# C128_Keyb_Test_SMD.net
KiCad netlist of a schematic drawn in EAGLE
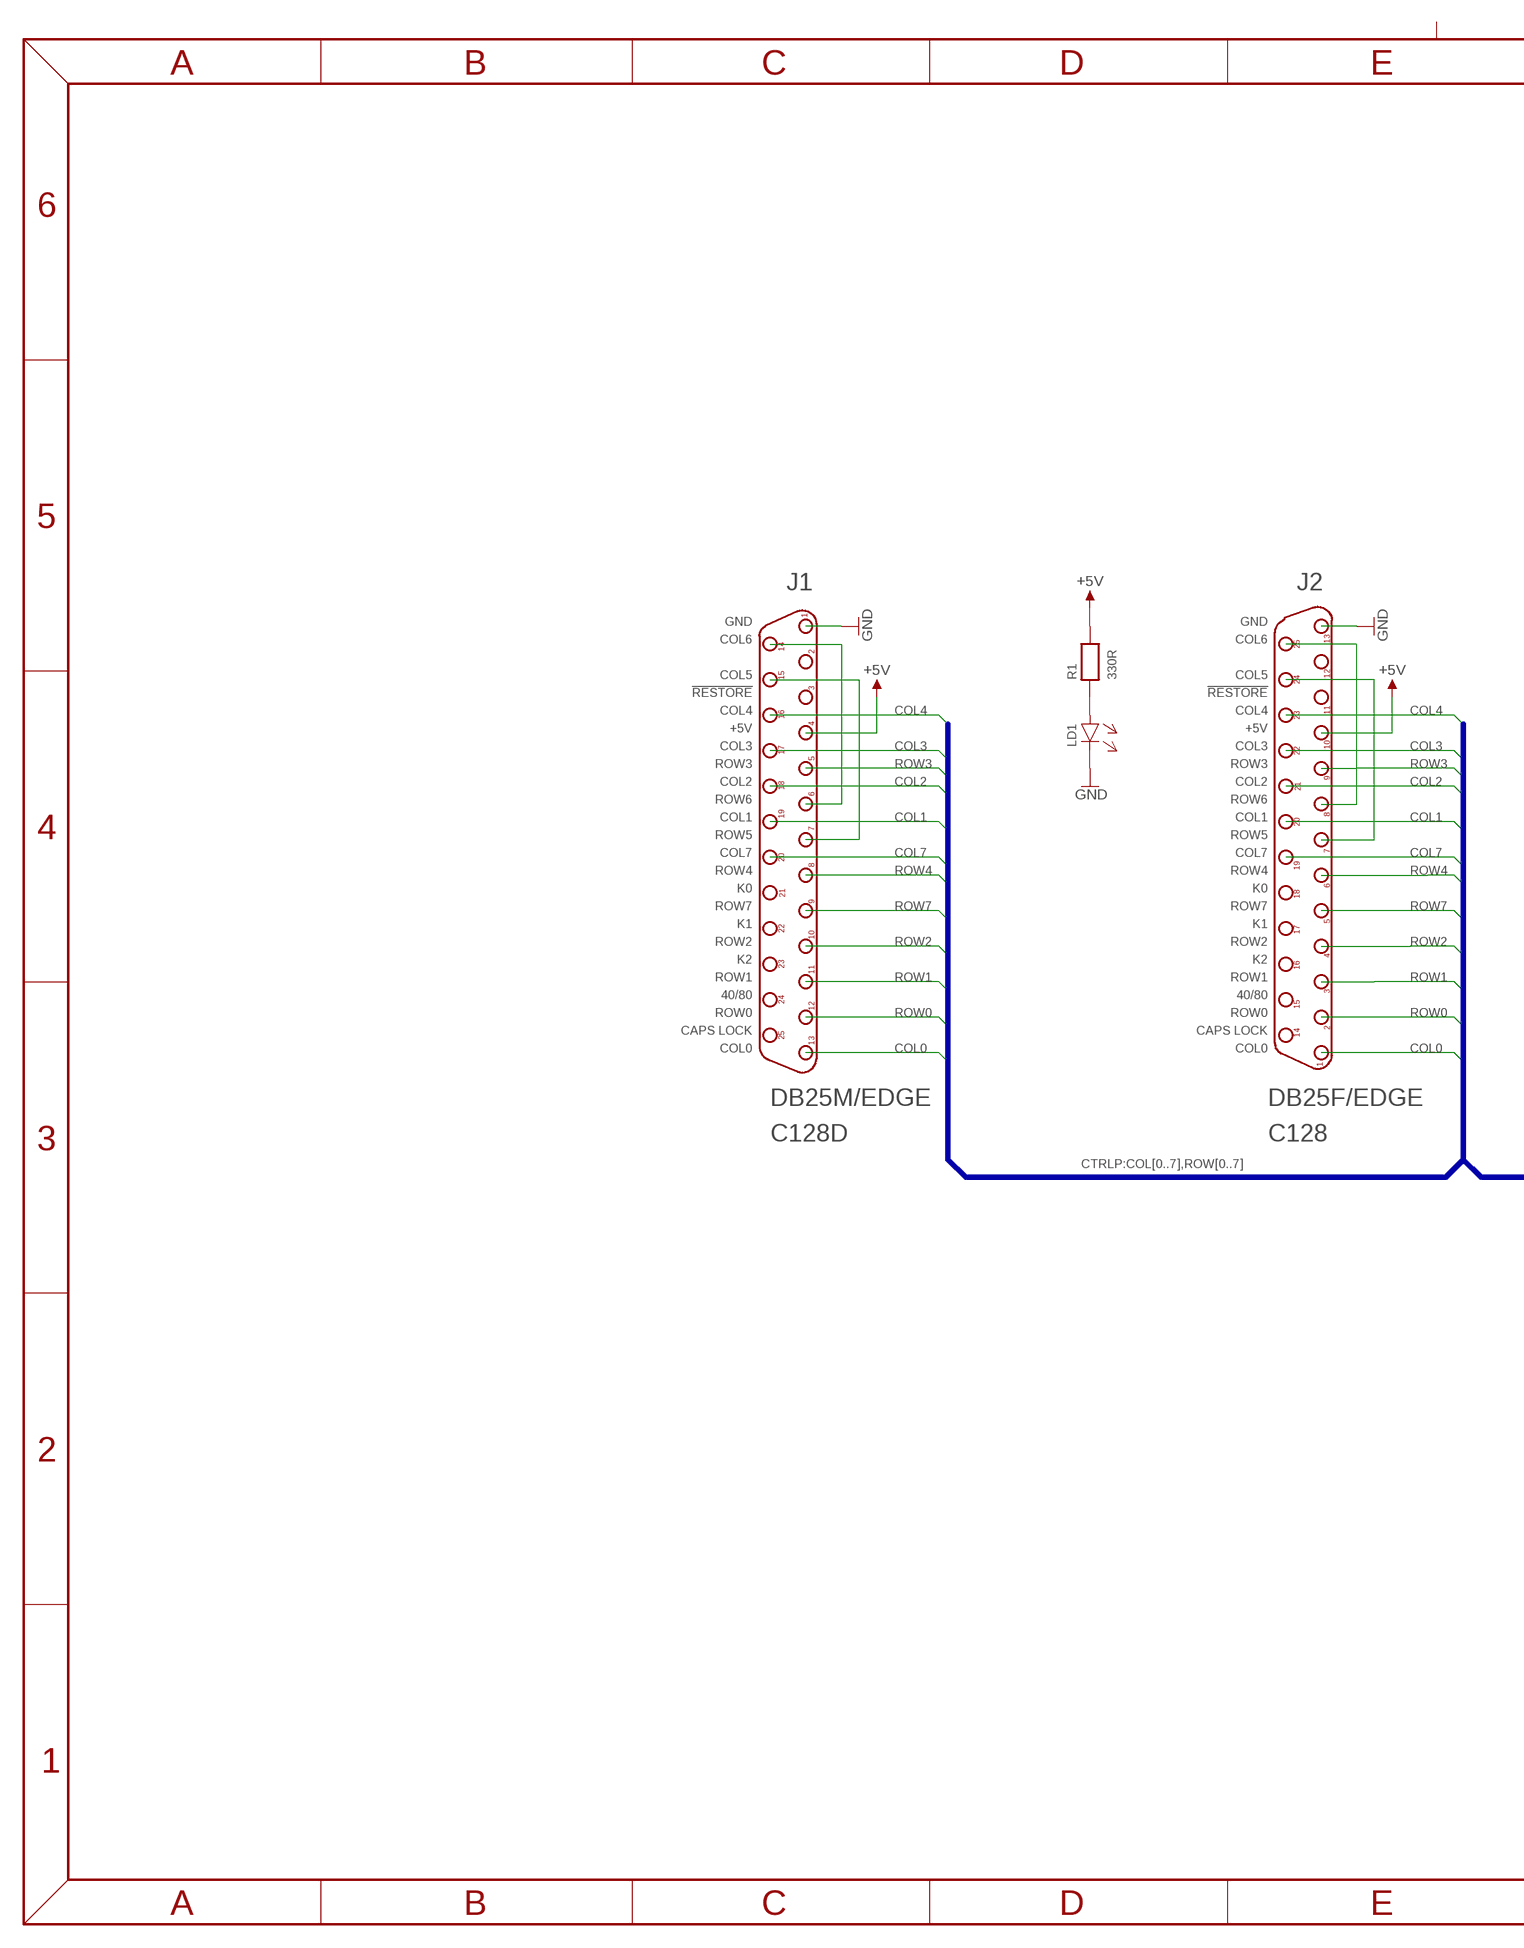
[diagram p0: schematic, sheet 1, part 1 of 2]
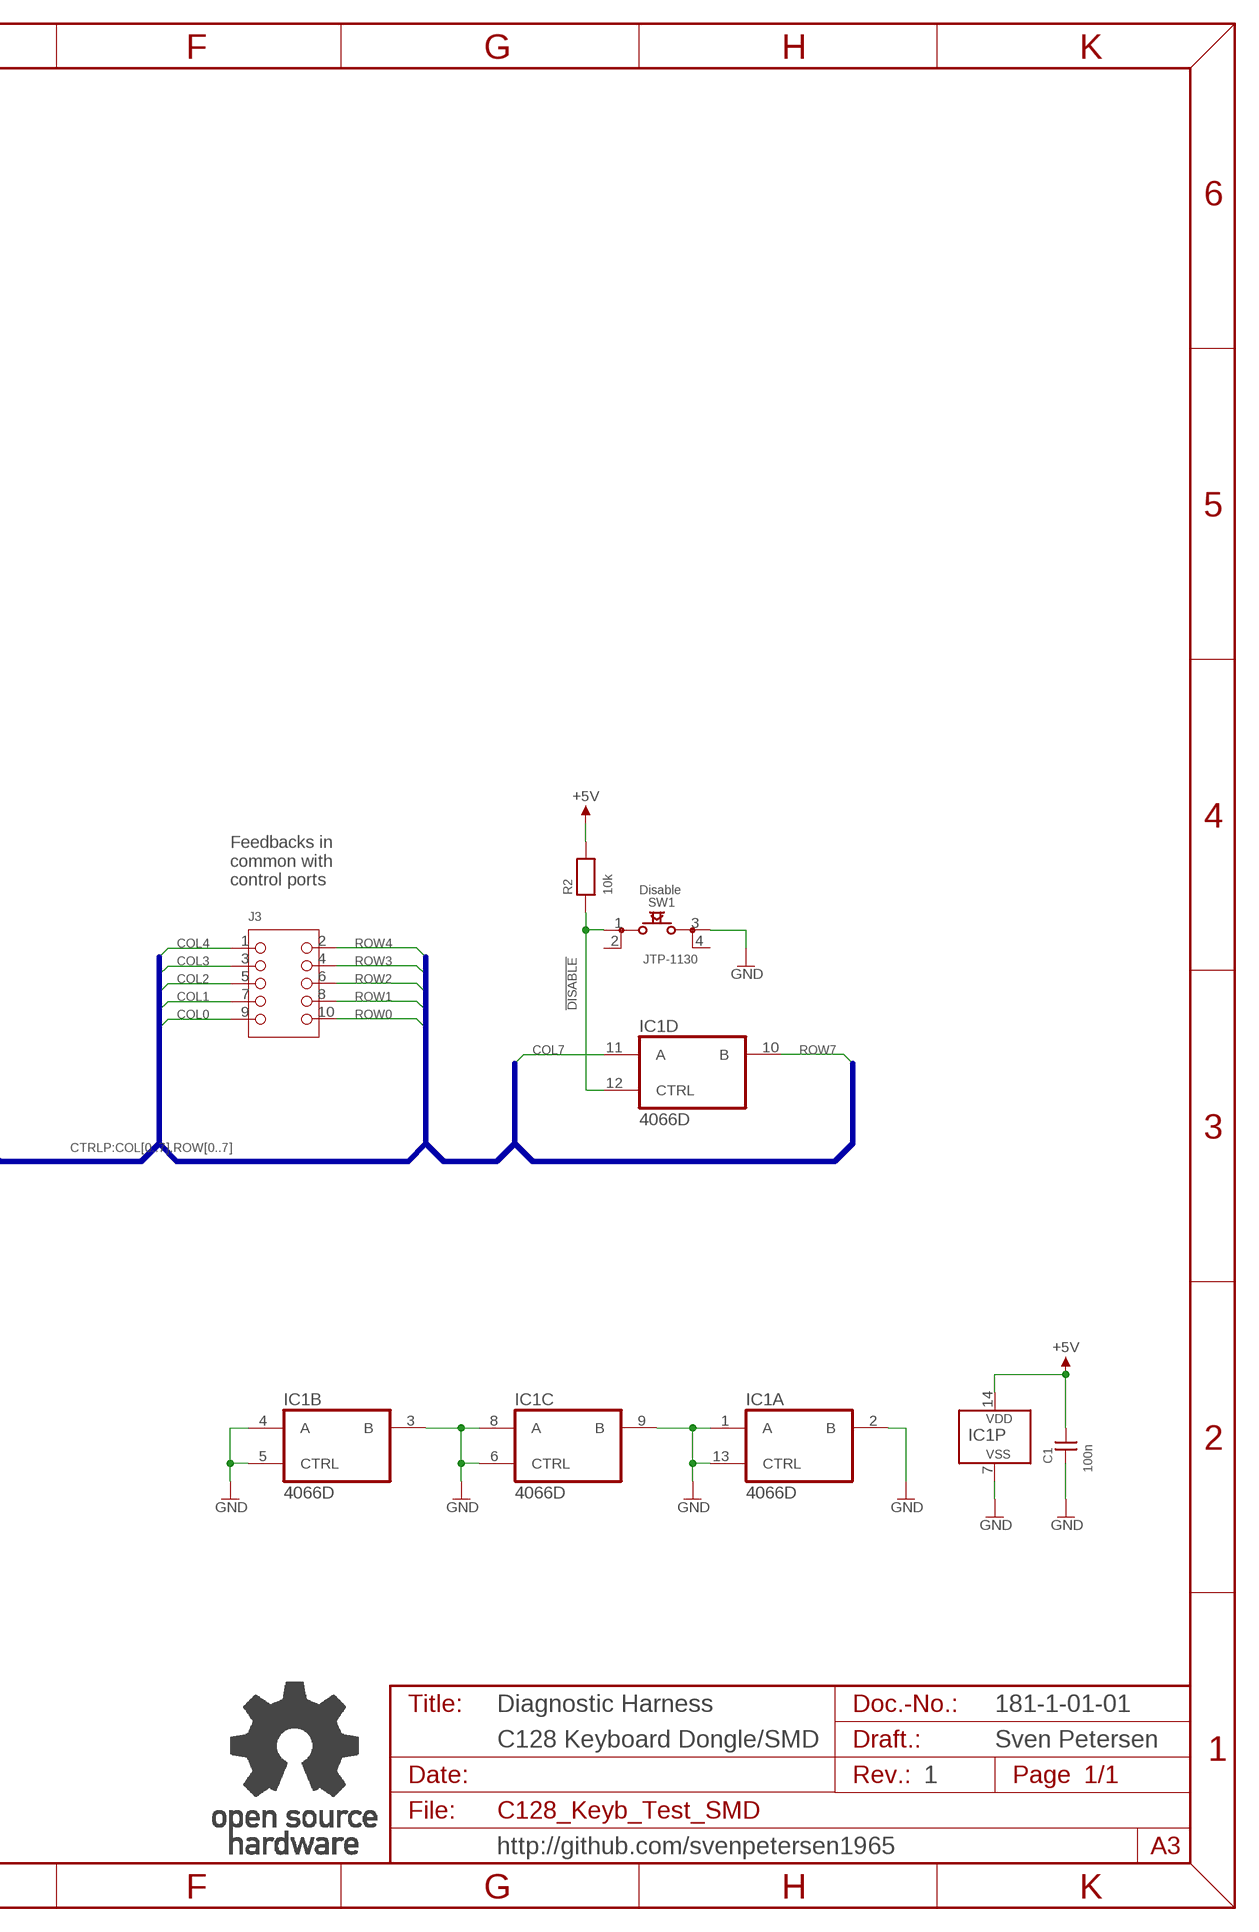
[diagram p1: schematic, sheet 1, part 2 of 2]

(export (version "E")
  (design (tool "Eeschema 10.0.6"))
  (components
    (comp (ref "C1")
      (value "100n")
      (footprint "eagle-import:0805")
      (libsource (lib "eagle-import") (part "CAP010805"))
    )
    (comp (ref "IC1")
      (value "4066D")
      (footprint "eagle-import:SO14")
      (libsource (lib "eagle-import") (part "4066D"))
    )
    (comp (ref "J1")
      (value "DB25M/EDGE")
      (footprint "eagle-import:DB25M-EDGE")
      (libsource (lib "eagle-import") (part "DB25M/EDGE"))
    )
    (comp (ref "J2")
      (value "DB25F/EDGE")
      (footprint "eagle-import:DB25F-EDGE")
      (libsource (lib "eagle-import") (part "DB25F/EDGE"))
    )
    (comp (ref "J3")
      (value "2X05WV")
      (footprint "eagle-import:2X05WV")
      (libsource (lib "eagle-import") (part "2X05WV"))
    )
    (comp (ref "LD1")
      (value "3MM")
      (footprint "eagle-import:3MM")
      (libsource (lib "eagle-import") (part "3MM"))
    )
    (comp (ref "R1")
      (value "330R")
      (footprint "eagle-import:0805")
      (libsource (lib "eagle-import") (part "RES040805"))
    )
    (comp (ref "R2")
      (value "10k")
      (footprint "eagle-import:0805")
      (libsource (lib "eagle-import") (part "RES040805"))
    )
    (comp (ref "SW1")
      (value "JTP-1130")
      (footprint "eagle-import:JTP-1130")
      (libsource (lib "eagle-import") (part "JTP-1130"))
    )
    (comp (ref "U$20")
      (value "OPEN_SOURCE_HW")
      (footprint "eagle-import:OPENHW")
      (libsource (lib "eagle-import") (part "OPEN_SOURCE_HW"))
    )
  )
  (nets
    (net (code "1") (name "+5V") (class "Default")
      (node (ref "C1") (pin "2") (pinfunction "2_2") (pintype "passive"))
      (node (ref "IC1") (pin "14") (pinfunction "VDD_14") (pintype "power_in"))
      (node (ref "J1") (pin "4") (pinfunction "4_4") (pintype "passive"))
      (node (ref "J2") (pin "10") (pinfunction "10_10") (pintype "passive"))
      (node (ref "R1") (pin "2") (pinfunction "2_2") (pintype "passive"))
      (node (ref "R2") (pin "2") (pinfunction "2_2") (pintype "passive"))
    )
    (net (code "2") (name "/COL0") (class "Default")
      (node (ref "J1") (pin "13") (pinfunction "13_13") (pintype "passive"))
      (node (ref "J2") (pin "1") (pinfunction "1_1") (pintype "passive"))
      (node (ref "J3") (pin "9") (pinfunction "9_9") (pintype "passive"))
    )
    (net (code "3") (name "/COL1") (class "Default")
      (node (ref "J1") (pin "19") (pinfunction "19_19") (pintype "passive"))
      (node (ref "J2") (pin "20") (pinfunction "20_20") (pintype "passive"))
      (node (ref "J3") (pin "7") (pinfunction "7_7") (pintype "passive"))
    )
    (net (code "4") (name "/COL2") (class "Default")
      (node (ref "J1") (pin "18") (pinfunction "18_18") (pintype "passive"))
      (node (ref "J2") (pin "21") (pinfunction "21_21") (pintype "passive"))
      (node (ref "J3") (pin "5") (pinfunction "5_5") (pintype "passive"))
    )
    (net (code "5") (name "/COL3") (class "Default")
      (node (ref "J1") (pin "17") (pinfunction "17_17") (pintype "passive"))
      (node (ref "J2") (pin "22") (pinfunction "22_22") (pintype "passive"))
      (node (ref "J3") (pin "3") (pinfunction "3_3") (pintype "passive"))
    )
    (net (code "6") (name "/COL4") (class "Default")
      (node (ref "J1") (pin "16") (pinfunction "16_16") (pintype "passive"))
      (node (ref "J2") (pin "23") (pinfunction "23_23") (pintype "passive"))
      (node (ref "J3") (pin "1") (pinfunction "1_1") (pintype "passive"))
    )
    (net (code "7") (name "/COL7") (class "Default")
      (node (ref "IC1") (pin "11") (pinfunction "A_11") (pintype "tri_state"))
      (node (ref "J1") (pin "20") (pinfunction "20_20") (pintype "passive"))
      (node (ref "J2") (pin "19") (pinfunction "19_19") (pintype "passive"))
    )
    (net (code "8") (name "/ROW0") (class "Default")
      (node (ref "J1") (pin "12") (pinfunction "12_12") (pintype "passive"))
      (node (ref "J2") (pin "2") (pinfunction "2_2") (pintype "passive"))
      (node (ref "J3") (pin "10") (pinfunction "10_10") (pintype "passive"))
    )
    (net (code "9") (name "/ROW1") (class "Default")
      (node (ref "J1") (pin "11") (pinfunction "11_11") (pintype "passive"))
      (node (ref "J2") (pin "3") (pinfunction "3_3") (pintype "passive"))
      (node (ref "J3") (pin "8") (pinfunction "8_8") (pintype "passive"))
    )
    (net (code "10") (name "/ROW2") (class "Default")
      (node (ref "J1") (pin "10") (pinfunction "10_10") (pintype "passive"))
      (node (ref "J2") (pin "4") (pinfunction "4_4") (pintype "passive"))
      (node (ref "J3") (pin "6") (pinfunction "6_6") (pintype "passive"))
    )
    (net (code "11") (name "/ROW3") (class "Default")
      (node (ref "J1") (pin "5") (pinfunction "5_5") (pintype "passive"))
      (node (ref "J2") (pin "9") (pinfunction "9_9") (pintype "passive"))
      (node (ref "J3") (pin "4") (pinfunction "4_4") (pintype "passive"))
    )
    (net (code "12") (name "/ROW4") (class "Default")
      (node (ref "J1") (pin "8") (pinfunction "8_8") (pintype "passive"))
      (node (ref "J2") (pin "6") (pinfunction "6_6") (pintype "passive"))
      (node (ref "J3") (pin "2") (pinfunction "2_2") (pintype "passive"))
    )
    (net (code "13") (name "/ROW7") (class "Default")
      (node (ref "IC1") (pin "10") (pinfunction "B_10") (pintype "tri_state"))
      (node (ref "J1") (pin "9") (pinfunction "9_9") (pintype "passive"))
      (node (ref "J2") (pin "5") (pinfunction "5_5") (pintype "passive"))
    )
    (net (code "15") (name "/~{DISABLE}") (class "Default")
      (node (ref "IC1") (pin "12") (pinfunction "CTRL_12") (pintype "input"))
      (node (ref "R2") (pin "1") (pinfunction "1_1") (pintype "passive"))
      (node (ref "SW1") (pin "1") (pinfunction "1_1") (pintype "passive"))
    )
    (net (code "16") (name "GND") (class "Default")
      (node (ref "C1") (pin "1") (pinfunction "1_1") (pintype "passive"))
      (node (ref "IC1") (pin "1") (pinfunction "A_1") (pintype "tri_state"))
      (node (ref "IC1") (pin "13") (pinfunction "CTRL_13") (pintype "input"))
      (node (ref "IC1") (pin "2") (pinfunction "B_2") (pintype "tri_state"))
      (node (ref "IC1") (pin "3") (pinfunction "B_3") (pintype "tri_state"))
      (node (ref "IC1") (pin "4") (pinfunction "A_4") (pintype "tri_state"))
      (node (ref "IC1") (pin "5") (pinfunction "CTRL_5") (pintype "input"))
      (node (ref "IC1") (pin "6") (pinfunction "CTRL_6") (pintype "input"))
      (node (ref "IC1") (pin "7") (pinfunction "VSS_7") (pintype "power_in"))
      (node (ref "IC1") (pin "8") (pinfunction "A_8") (pintype "tri_state"))
      (node (ref "IC1") (pin "9") (pinfunction "B_9") (pintype "tri_state"))
      (node (ref "J1") (pin "1") (pinfunction "1_1") (pintype "passive"))
      (node (ref "J2") (pin "13") (pinfunction "13_13") (pintype "passive"))
      (node (ref "LD1") (pin "C") (pinfunction "K_C") (pintype "bidirectional"))
      (node (ref "SW1") (pin "3") (pinfunction "3_3") (pintype "passive"))
    )
    (net (code "17") (name "Net-(J1-Pad14)") (class "Default")
      (node (ref "J1") (pin "14") (pinfunction "14_14") (pintype "passive"))
      (node (ref "J1") (pin "6") (pinfunction "6_6") (pintype "passive"))
    )
    (net (code "18") (name "Net-(J1-Pad15)") (class "Default")
      (node (ref "J1") (pin "15") (pinfunction "15_15") (pintype "passive"))
      (node (ref "J1") (pin "7") (pinfunction "7_7") (pintype "passive"))
    )
    (net (code "19") (name "Net-(J2-Pad24)") (class "Default")
      (node (ref "J2") (pin "24") (pinfunction "24_24") (pintype "passive"))
      (node (ref "J2") (pin "7") (pinfunction "7_7") (pintype "passive"))
    )
    (net (code "20") (name "Net-(J2-Pad25)") (class "Default")
      (node (ref "J2") (pin "25") (pinfunction "25_25") (pintype "passive"))
      (node (ref "J2") (pin "8") (pinfunction "8_8") (pintype "passive"))
    )
    (net (code "21") (name "Net-(LD1-PadA)") (class "Default")
      (node (ref "LD1") (pin "A") (pinfunction "A_A") (pintype "bidirectional"))
      (node (ref "R1") (pin "1") (pinfunction "1_1") (pintype "passive"))
    )
    (net (code "22") (name "unconnected-(J1-Pad2)") (class "Default")
      (node (ref "J1") (pin "2") (pinfunction "2_2") (pintype "passive"))
    )
    (net (code "23") (name "unconnected-(J1-Pad3)") (class "Default")
      (node (ref "J1") (pin "3") (pinfunction "3_3") (pintype "passive"))
    )
    (net (code "24") (name "unconnected-(J1-Pad21)") (class "Default")
      (node (ref "J1") (pin "21") (pinfunction "21_21") (pintype "passive"))
    )
    (net (code "25") (name "unconnected-(J1-Pad22)") (class "Default")
      (node (ref "J1") (pin "22") (pinfunction "22_22") (pintype "passive"))
    )
    (net (code "26") (name "unconnected-(J1-Pad23)") (class "Default")
      (node (ref "J1") (pin "23") (pinfunction "23_23") (pintype "passive"))
    )
    (net (code "27") (name "unconnected-(J1-Pad24)") (class "Default")
      (node (ref "J1") (pin "24") (pinfunction "24_24") (pintype "passive"))
    )
    (net (code "28") (name "unconnected-(J1-Pad25)") (class "Default")
      (node (ref "J1") (pin "25") (pinfunction "25_25") (pintype "passive"))
    )
    (net (code "29") (name "unconnected-(J2-Pad11)") (class "Default")
      (node (ref "J2") (pin "11") (pinfunction "11_11") (pintype "passive"))
    )
    (net (code "30") (name "unconnected-(J2-Pad12)") (class "Default")
      (node (ref "J2") (pin "12") (pinfunction "12_12") (pintype "passive"))
    )
    (net (code "31") (name "unconnected-(J2-Pad14)") (class "Default")
      (node (ref "J2") (pin "14") (pinfunction "14_14") (pintype "passive"))
    )
    (net (code "32") (name "unconnected-(J2-Pad15)") (class "Default")
      (node (ref "J2") (pin "15") (pinfunction "15_15") (pintype "passive"))
    )
    (net (code "33") (name "unconnected-(J2-Pad16)") (class "Default")
      (node (ref "J2") (pin "16") (pinfunction "16_16") (pintype "passive"))
    )
    (net (code "34") (name "unconnected-(J2-Pad17)") (class "Default")
      (node (ref "J2") (pin "17") (pinfunction "17_17") (pintype "passive"))
    )
    (net (code "35") (name "unconnected-(J2-Pad18)") (class "Default")
      (node (ref "J2") (pin "18") (pinfunction "18_18") (pintype "passive"))
    )
    (net (code "36") (name "unconnected-(SW1-Pad2)") (class "Default")
      (node (ref "SW1") (pin "2") (pinfunction "2_2") (pintype "passive"))
    )
    (net (code "37") (name "unconnected-(SW1-Pad4)") (class "Default")
      (node (ref "SW1") (pin "4") (pinfunction "4_4") (pintype "passive"))
    )
  )
)
